# 5_-OPI_MAIN.net
KiCad netlist of a schematic drawn in Altium Designer
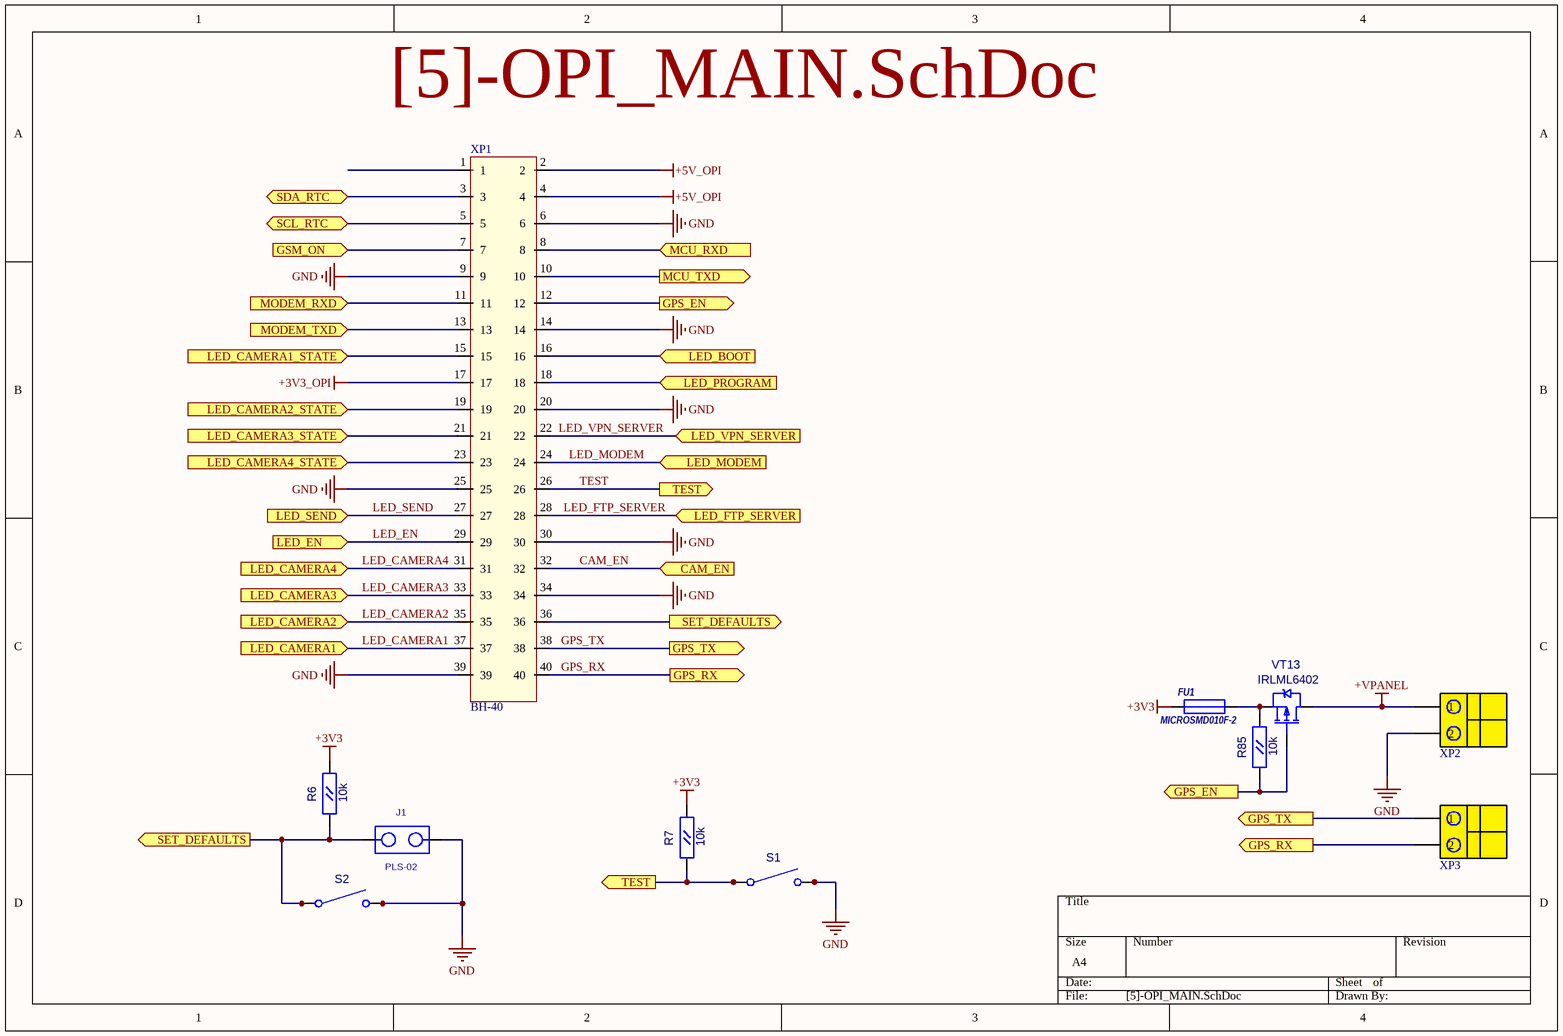
[diagram p0: [5]-OPI_MAIN.SchDoc]

(export (version "E")
  (design (tool "Eeschema 10.0.6"))
  (components
    (comp (ref "FU1")
      (value "MICROSMD010F-2")
      (footprint "RC1210")
      (description "MICROSMD")
      (libsource (lib "fizik_lib") (part "MICROSMD"))
    )
    (comp (ref "J1") (value "PLS-02") (footprint "PLS-02") (libsource (lib "fizik_lib") (part "PLS-02")))
    (comp (ref "R6")
      (value "10k")
      (footprint "RC0603")
      (description "RC0603")
      (libsource (lib "fizik_lib") (part "RC0603"))
    )
    (comp (ref "R7")
      (value "10k")
      (footprint "RC0603")
      (description "RC0603")
      (libsource (lib "fizik_lib") (part "RC0603"))
    )
    (comp (ref "R85")
      (value "10k")
      (footprint "RC0603")
      (description "RC0603")
      (libsource (lib "fizik_lib") (part "RC0603"))
    )
    (comp (ref "S1")
      (value "DTSM-61N")
      (footprint "DTSM-61N")
      (description "Switch, Single Pole, Single Throw, Normally Open")
      (libsource (lib "fizik_lib") (part "DTSM-61N"))
    )
    (comp (ref "S2")
      (value "DTSM-61N")
      (footprint "DTSM-61N")
      (description "Switch, Single Pole, Single Throw, Normally Open")
      (libsource (lib "fizik_lib") (part "DTSM-61N"))
    )
    (comp (ref "VT13")
      (value "IRLML6402")
      (footprint "SOT-23(123)")
      (description "HEXFET Power MOSFET")
      (libsource (lib "gprs_modem_2") (part "IRLML6402"))
    )
    (comp (ref "XP1")
      (value "BH-40")
      (footprint "BH-40")
      (description "2.54mm connector with key")
      (libsource (lib "fizik_lib") (part "BH-40"))
    )
    (comp (ref "XP2")
      (value "DG330-2P")
      (footprint "DG330-2P")
      (description "Degson 2 pin connector rear")
      (libsource (lib "fizik_lib") (part "DG330-2P"))
    )
    (comp (ref "XP3")
      (value "DG330-2P")
      (footprint "DG330-2P")
      (description "Degson 2 pin connector rear")
      (libsource (lib "fizik_lib") (part "DG330-2P"))
    )
  )
  (nets
    (net (code "1") (name "+3V3") (class "Default")
      (node (ref "FU1") (pin "1") (pintype "passive"))
      (node (ref "R6") (pin "2") (pinfunction "B_2") (pintype "passive"))
      (node (ref "R7") (pin "2") (pinfunction "B_2") (pintype "passive"))
    )
    (net (code "2") (name "+3V3_OPI") (class "Default")
      (node (ref "XP1") (pin "17") (pinfunction "17_17") (pintype "passive"))
    )
    (net (code "3") (name "+5V_OPI") (class "Default")
      (node (ref "XP1") (pin "2") (pinfunction "2_2") (pintype "passive"))
      (node (ref "XP1") (pin "4") (pinfunction "4_4") (pintype "passive"))
    )
    (net (code "4") (name "+VPANEL") (class "Default")
      (node (ref "VT13") (pin "3") (pinfunction "D_3") (pintype "passive"))
      (node (ref "XP2") (pin "1") (pinfunction "1_1") (pintype "passive"))
    )
    (net (code "5") (name "/CAM_EN") (class "Default")
      (node (ref "XP1") (pin "32") (pinfunction "32_32") (pintype "passive"))
    )
    (net (code "6") (name "/GPS_EN") (class "Default")
      (node (ref "R85") (pin "1") (pinfunction "A_1") (pintype "passive"))
      (node (ref "VT13") (pin "1") (pinfunction "G_1") (pintype "passive"))
      (node (ref "XP1") (pin "12") (pinfunction "12_12") (pintype "passive"))
    )
    (net (code "7") (name "/GPS_RX") (class "Default")
      (node (ref "XP1") (pin "40") (pinfunction "40_40") (pintype "passive"))
      (node (ref "XP3") (pin "2") (pinfunction "2_2") (pintype "passive"))
    )
    (net (code "8") (name "/GPS_TX") (class "Default")
      (node (ref "XP1") (pin "38") (pinfunction "38_38") (pintype "passive"))
      (node (ref "XP3") (pin "1") (pinfunction "1_1") (pintype "passive"))
    )
    (net (code "9") (name "/GSM_ON") (class "Default")
      (node (ref "XP1") (pin "7") (pinfunction "7_7") (pintype "passive"))
    )
    (net (code "10") (name "/LED_BOOT") (class "Default")
      (node (ref "XP1") (pin "16") (pinfunction "16_16") (pintype "passive"))
    )
    (net (code "11") (name "/LED_CAMERA1") (class "Default")
      (node (ref "XP1") (pin "37") (pinfunction "37_37") (pintype "passive"))
    )
    (net (code "12") (name "/LED_CAMERA1_STATE") (class "Default")
      (node (ref "XP1") (pin "15") (pinfunction "15_15") (pintype "passive"))
    )
    (net (code "13") (name "/LED_CAMERA2") (class "Default")
      (node (ref "XP1") (pin "35") (pinfunction "35_35") (pintype "passive"))
    )
    (net (code "14") (name "/LED_CAMERA2_STATE") (class "Default")
      (node (ref "XP1") (pin "19") (pinfunction "19_19") (pintype "passive"))
    )
    (net (code "15") (name "/LED_CAMERA3") (class "Default")
      (node (ref "XP1") (pin "33") (pinfunction "33_33") (pintype "passive"))
    )
    (net (code "16") (name "/LED_CAMERA3_STATE") (class "Default")
      (node (ref "XP1") (pin "21") (pinfunction "21_21") (pintype "passive"))
    )
    (net (code "17") (name "/LED_CAMERA4") (class "Default")
      (node (ref "XP1") (pin "31") (pinfunction "31_31") (pintype "passive"))
    )
    (net (code "18") (name "/LED_CAMERA4_STATE") (class "Default")
      (node (ref "XP1") (pin "23") (pinfunction "23_23") (pintype "passive"))
    )
    (net (code "19") (name "/LED_EN") (class "Default")
      (node (ref "XP1") (pin "29") (pinfunction "29_29") (pintype "passive"))
    )
    (net (code "20") (name "/LED_FTP_SERVER") (class "Default")
      (node (ref "XP1") (pin "28") (pinfunction "28_28") (pintype "passive"))
    )
    (net (code "21") (name "/LED_MODEM") (class "Default")
      (node (ref "XP1") (pin "24") (pinfunction "24_24") (pintype "passive"))
    )
    (net (code "22") (name "/LED_PROGRAM") (class "Default")
      (node (ref "XP1") (pin "18") (pinfunction "18_18") (pintype "passive"))
    )
    (net (code "23") (name "/LED_SEND") (class "Default")
      (node (ref "XP1") (pin "27") (pinfunction "27_27") (pintype "passive"))
    )
    (net (code "24") (name "/LED_VPN_SERVER") (class "Default")
      (node (ref "XP1") (pin "22") (pinfunction "22_22") (pintype "passive"))
    )
    (net (code "25") (name "/MCU_RXD") (class "Default")
      (node (ref "XP1") (pin "8") (pinfunction "8_8") (pintype "passive"))
    )
    (net (code "26") (name "/MCU_TXD") (class "Default")
      (node (ref "XP1") (pin "10") (pinfunction "10_10") (pintype "passive"))
    )
    (net (code "27") (name "/MODEM_RXD") (class "Default")
      (node (ref "XP1") (pin "11") (pinfunction "11_11") (pintype "passive"))
    )
    (net (code "28") (name "/MODEM_TXD") (class "Default")
      (node (ref "XP1") (pin "13") (pinfunction "13_13") (pintype "passive"))
    )
    (net (code "29") (name "/SCL_RTC") (class "Default")
      (node (ref "XP1") (pin "5") (pinfunction "5_5") (pintype "passive"))
    )
    (net (code "30") (name "/SDA_RTC") (class "Default")
      (node (ref "XP1") (pin "3") (pinfunction "3_3") (pintype "passive"))
    )
    (net (code "31") (name "/SET_DEFAULTS") (class "Default")
      (node (ref "J1") (pin "1") (pintype "passive"))
      (node (ref "R6") (pin "1") (pinfunction "A_1") (pintype "passive"))
      (node (ref "S2") (pin "1") (pinfunction "C1_1") (pintype "passive"))
      (node (ref "S2") (pin "2") (pintype "passive"))
      (node (ref "XP1") (pin "36") (pinfunction "36_36") (pintype "passive"))
    )
    (net (code "32") (name "/TEST") (class "Default")
      (node (ref "R7") (pin "1") (pinfunction "A_1") (pintype "passive"))
      (node (ref "S1") (pin "1") (pinfunction "C1_1") (pintype "passive"))
      (node (ref "S1") (pin "2") (pintype "passive"))
      (node (ref "XP1") (pin "26") (pinfunction "26_26") (pintype "passive"))
    )
    (net (code "33") (name "GND") (class "Default")
      (node (ref "J1") (pin "2") (pintype "passive"))
      (node (ref "S1") (pin "3") (pinfunction "C2_3") (pintype "passive"))
      (node (ref "S1") (pin "4") (pintype "passive"))
      (node (ref "S2") (pin "3") (pinfunction "C2_3") (pintype "passive"))
      (node (ref "S2") (pin "4") (pintype "passive"))
      (node (ref "XP1") (pin "14") (pinfunction "14_14") (pintype "passive"))
      (node (ref "XP1") (pin "20") (pinfunction "20_20") (pintype "passive"))
      (node (ref "XP1") (pin "25") (pinfunction "25_25") (pintype "passive"))
      (node (ref "XP1") (pin "30") (pinfunction "30_30") (pintype "passive"))
      (node (ref "XP1") (pin "34") (pinfunction "34_34") (pintype "passive"))
      (node (ref "XP1") (pin "39") (pinfunction "39_39") (pintype "passive"))
      (node (ref "XP1") (pin "6") (pinfunction "6_6") (pintype "passive"))
      (node (ref "XP1") (pin "9") (pinfunction "9_9") (pintype "passive"))
      (node (ref "XP2") (pin "2") (pinfunction "2_2") (pintype "passive"))
    )
    (net (code "34") (name "Net-(R85-B)") (class "Default")
      (node (ref "FU1") (pin "2") (pintype "passive"))
      (node (ref "R85") (pin "2") (pinfunction "B_2") (pintype "passive"))
      (node (ref "VT13") (pin "2") (pinfunction "S_2") (pintype "passive"))
    )
    (net (code "35") (name "unconnected-(XP1-Pad1)") (class "Default")
      (node (ref "XP1") (pin "1") (pinfunction "1_1") (pintype "passive"))
    )
  )
)
